# 1-Schematic_GPS_data_logger.net
KiCad netlist of a schematic drawn in EasyEDA
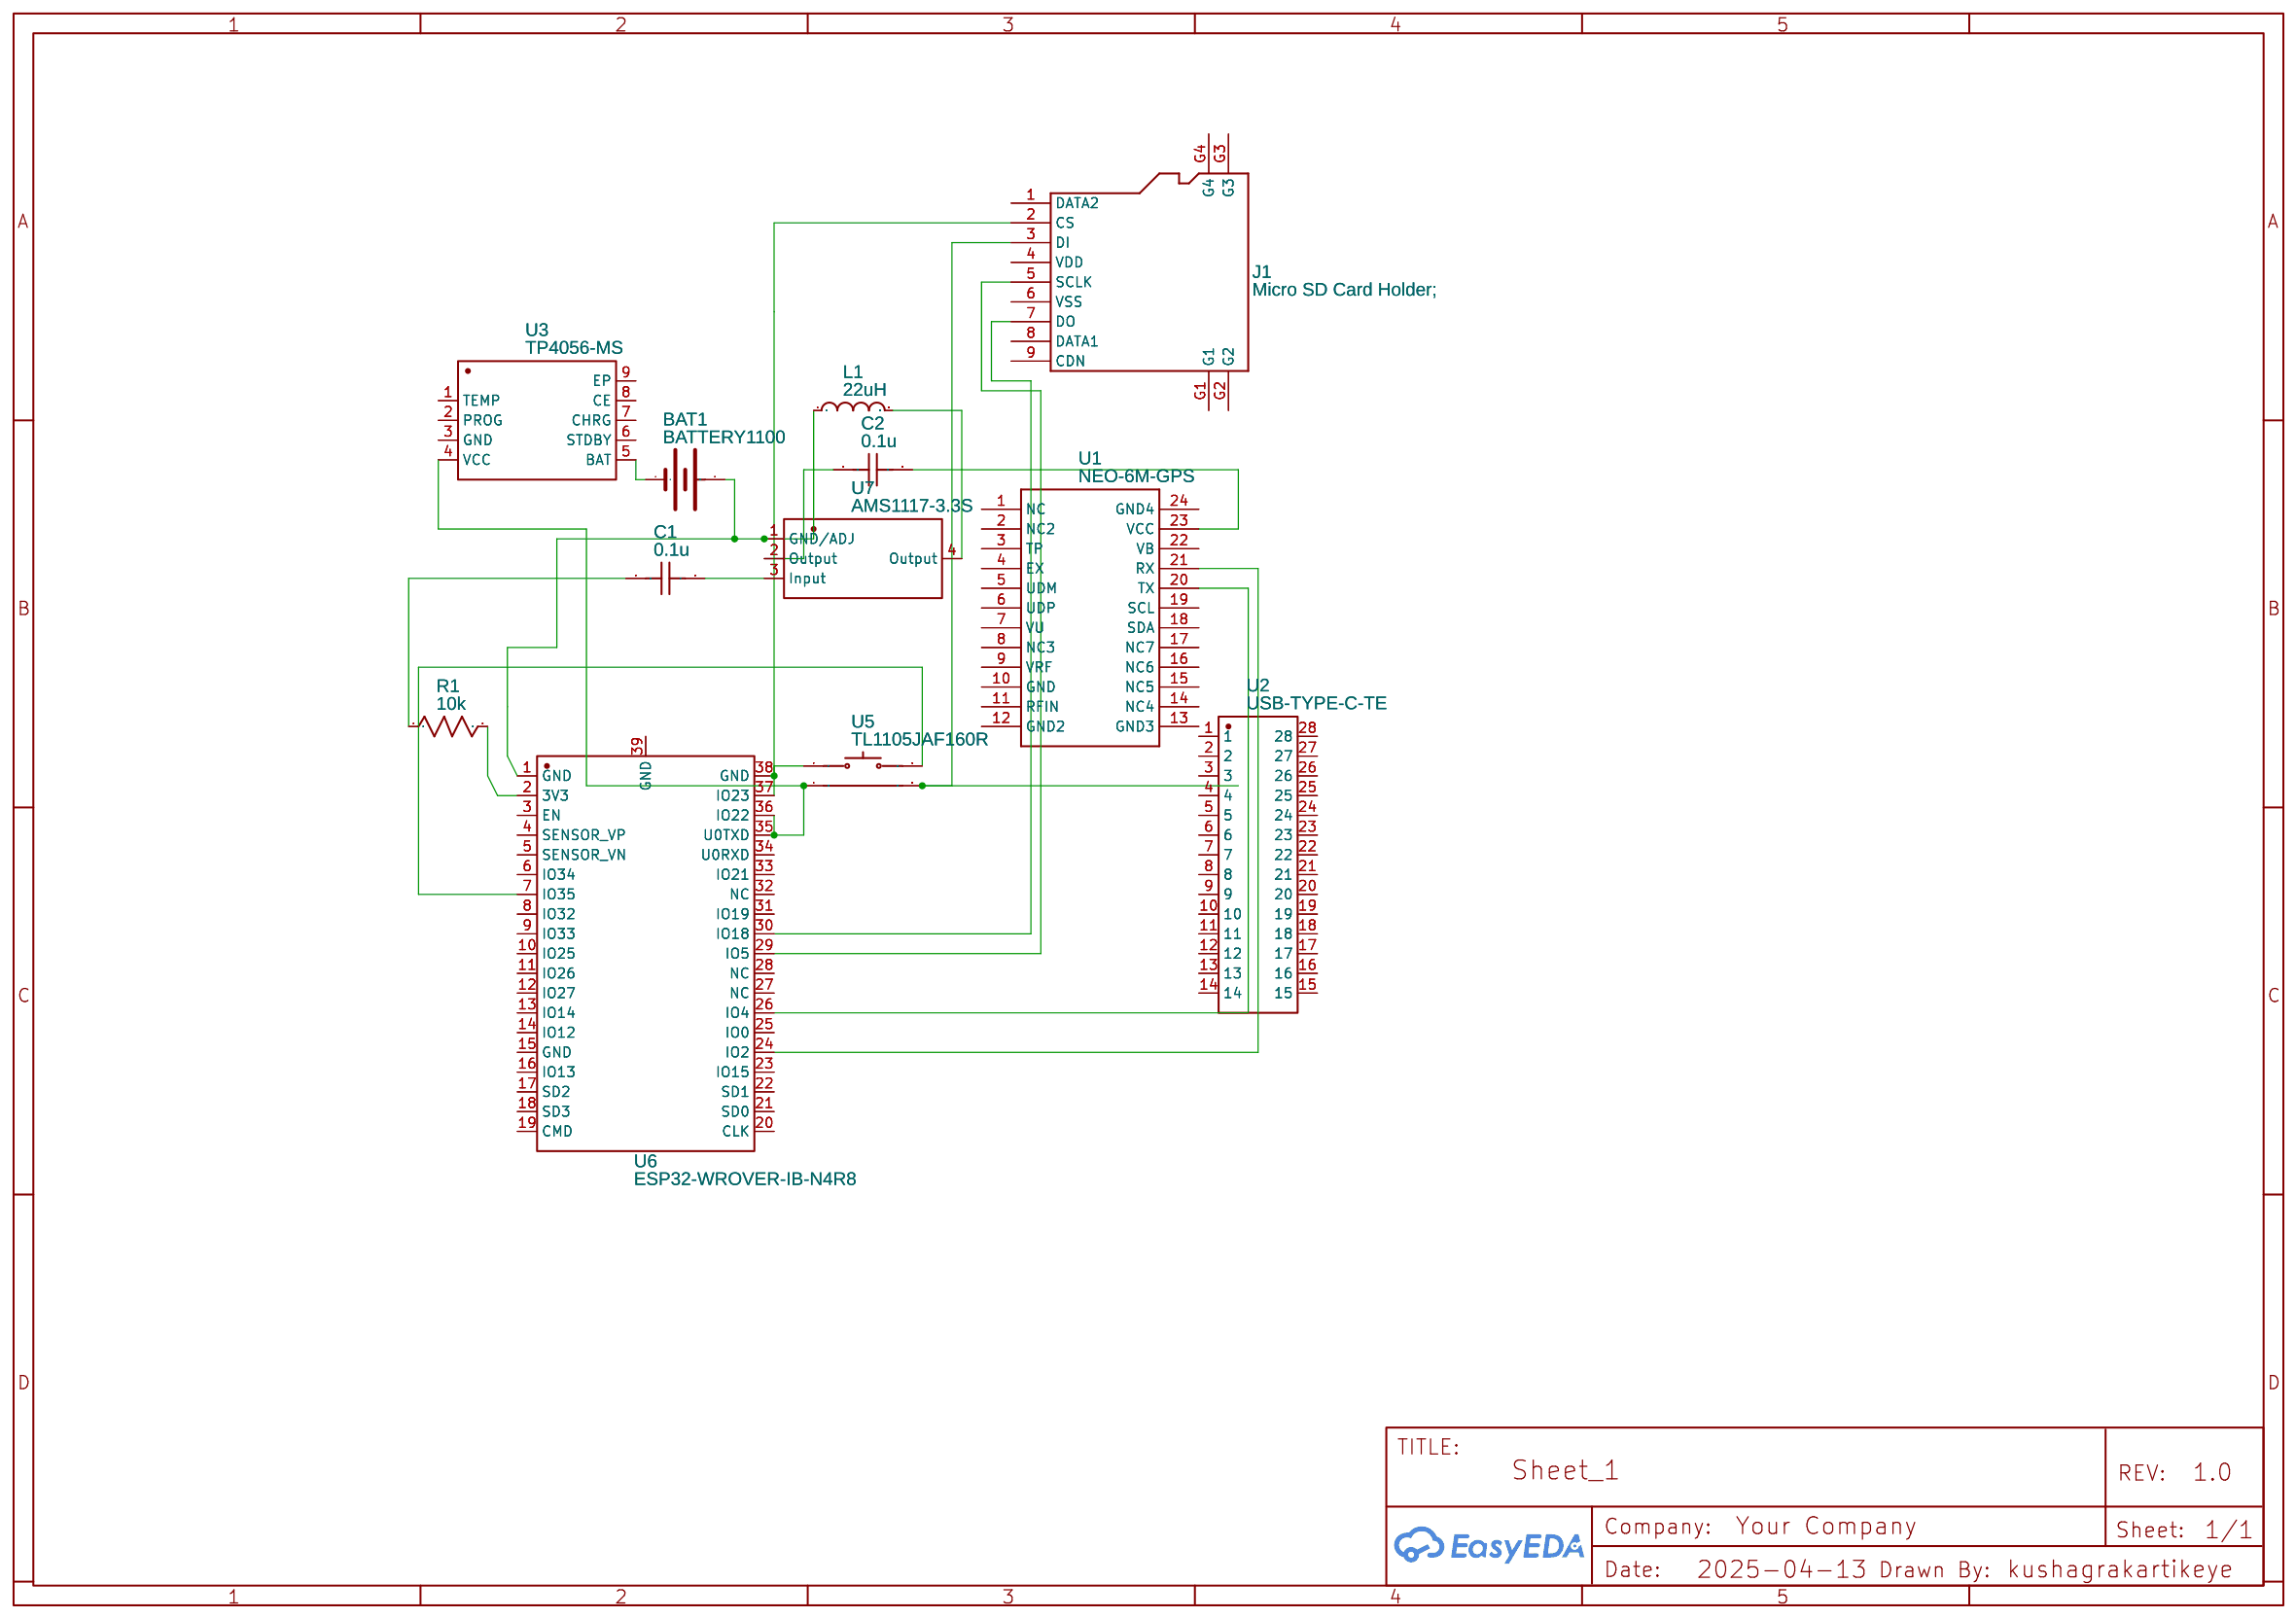
[diagram p0: schematic sheet]

(export (version "E")
  (design (tool "Eeschema 10.0.6"))
  (components
    (comp (ref "BAT1") (value "BATTERY1100") (libsource (lib "") (part "BATTERY1100")))
    (comp (ref "C1") (value "0.1u") (libsource (lib "") (part "C_0603_US")))
    (comp (ref "C2") (value "0.1u") (libsource (lib "") (part "C_0603_US")))
    (comp (ref "J1")
      (value "Micro SD Card Holder;")
      (fields (field (name "Manufacturer Part") "?"))
      (libsource (lib "") (part "Micro SD Card Holder;"))
    )
    (comp (ref "L1")
      (value "22uH")
      (fields
        (field (name "Manufacturer Part") "SSD1306-220MT")
        (field (name "Manufacturer") "LanTu Micro(蓝图微电)")
      )
      (libsource (lib "") (part "SSD1306-220MT"))
    )
    (comp (ref "R1") (value "10k") (libsource (lib "") (part "R_0603_US")))
    (comp (ref "U1") (value "NEO-6M-GPS") (libsource (lib "") (part "NEO-6M-GPS")))
    (comp (ref "U2") (value "USB-TYPE-C-TE") (libsource (lib "") (part "USB-TYPE-C-TE")))
    (comp (ref "U3")
      (value "TP4056-MS")
      (fields (field (name "Manufacturer") "MSKSEMI(美森科)"))
      (libsource (lib "") (part "TP4056-MS"))
    )
    (comp (ref "U5")
      (value "TL1105JAF160R")
      (fields (field (name "Manufacturer") "E-Switch"))
      (libsource (lib "") (part "TL1105JAF160R"))
    )
    (comp (ref "U6")
      (value "ESP32-WROVER-IB-N4R8")
      (fields (field (name "Manufacturer") "ESPRESSIF(乐鑫)"))
      (libsource (lib "") (part "ESP32-WROVER-IB-N4R8"))
    )
    (comp (ref "U7")
      (value "AMS1117-3.3S")
      (fields (field (name "Manufacturer") "KEXIN(科信)"))
      (libsource (lib "") (part "AMS1117-3.3S"))
    )
  )
  (nets
    (net (code "1") (name "Net-(C1-Pad1)") (class "Default")
      (node (ref "C1") (pin "1") (pinfunction "1_1") (pintype "unspecified"))
      (node (ref "R1") (pin "1") (pinfunction "1_1") (pintype "unspecified"))
    )
    (net (code "2") (name "Net-(C2-Pad1)") (class "Default")
      (node (ref "C2") (pin "1") (pinfunction "1_1") (pintype "unspecified"))
      (node (ref "U7") (pin "2") (pinfunction "Output_2") (pintype "unspecified"))
    )
    (net (code "3") (name "Net-(J1-CS)") (class "Default")
      (node (ref "J1") (pin "2") (pinfunction "CS_2") (pintype "unspecified"))
      (node (ref "U5") (pin "1") (pinfunction "1_1") (pintype "input"))
      (node (ref "U6") (pin "37") (pinfunction "IO23_37") (pintype "unspecified"))
      (node (ref "U6") (pin "38") (pinfunction "GND_38") (pintype "unspecified"))
    )
    (net (code "4") (name "Net-(J1-DI)") (class "Default")
      (node (ref "J1") (pin "3") (pinfunction "DI_3") (pintype "unspecified"))
      (node (ref "U5") (pin "3") (pinfunction "3_3") (pintype "input"))
    )
    (net (code "5") (name "Net-(J1-DO)") (class "Default")
      (node (ref "J1") (pin "7") (pinfunction "DO_7") (pintype "unspecified"))
      (node (ref "U6") (pin "30") (pinfunction "IO18_30") (pintype "unspecified"))
    )
    (net (code "6") (name "Net-(J1-SCLK)") (class "Default")
      (node (ref "J1") (pin "5") (pinfunction "SCLK_5") (pintype "unspecified"))
      (node (ref "U6") (pin "29") (pinfunction "IO5_29") (pintype "unspecified"))
    )
    (net (code "7") (name "Net-(L1-Pad2)") (class "Default")
      (node (ref "L1") (pin "2") (pinfunction "2_2") (pintype "unspecified"))
      (node (ref "U7") (pin "4") (pinfunction "Output_4") (pintype "unspecified"))
    )
    (net (code "8") (name "Net-(U1-RX)") (class "Default")
      (node (ref "U1") (pin "21") (pinfunction "RX_21") (pintype "unspecified"))
      (node (ref "U6") (pin "24") (pinfunction "IO2_24") (pintype "unspecified"))
    )
    (net (code "9") (name "Net-(U1-TX)") (class "Default")
      (node (ref "U1") (pin "20") (pinfunction "TX_20") (pintype "unspecified"))
      (node (ref "U6") (pin "26") (pinfunction "IO4_26") (pintype "unspecified"))
    )
    (net (code "10") (name "Net-(U1-VCC)") (class "Default")
      (node (ref "C2") (pin "2") (pinfunction "2_2") (pintype "unspecified"))
      (node (ref "U1") (pin "23") (pinfunction "VCC_23") (pintype "unspecified"))
    )
    (net (code "11") (name "Net-(U3-BAT)") (class "Default")
      (node (ref "BAT1") (pin "-") (pinfunction "-_-") (pintype "passive"))
      (node (ref "U3") (pin "5") (pinfunction "BAT_5") (pintype "unspecified"))
    )
    (net (code "12") (name "Net-(U3-VCC)") (class "Default")
      (node (ref "U3") (pin "4") (pinfunction "VCC_4") (pintype "unspecified"))
      (node (ref "U5") (pin "4") (pinfunction "4_4") (pintype "input"))
      (node (ref "U6") (pin "35") (pinfunction "U0TXD_35") (pintype "unspecified"))
      (node (ref "U6") (pin "36") (pinfunction "IO22_36") (pintype "unspecified"))
    )
    (net (code "13") (name "Net-(U6-3V3)") (class "Default")
      (node (ref "R1") (pin "2") (pinfunction "2_2") (pintype "unspecified"))
      (node (ref "U6") (pin "2") (pinfunction "3V3_2") (pintype "unspecified"))
    )
    (net (code "14") (name "Net-(U6-IO35)") (class "Default")
      (node (ref "U5") (pin "2") (pinfunction "2_2") (pintype "input"))
      (node (ref "U6") (pin "7") (pinfunction "IO35_7") (pintype "unspecified"))
    )
    (net (code "15") (name "Net-(U7-GND{slash}ADJ)") (class "Default")
      (node (ref "BAT1") (pin "+") (pinfunction "+_+") (pintype "passive"))
      (node (ref "L1") (pin "1") (pinfunction "1_1") (pintype "unspecified"))
      (node (ref "U6") (pin "1") (pinfunction "GND_1") (pintype "unspecified"))
      (node (ref "U7") (pin "1") (pinfunction "GND/ADJ_1") (pintype "unspecified"))
    )
    (net (code "16") (name "Net-(U7-Input)") (class "Default")
      (node (ref "C1") (pin "2") (pinfunction "2_2") (pintype "unspecified"))
      (node (ref "U7") (pin "3") (pinfunction "Input_3") (pintype "unspecified"))
    )
    (net (code "17") (name "unconnected-(J1-CDN-Pad9)") (class "Default")
      (node (ref "J1") (pin "9") (pinfunction "CDN_9") (pintype "unspecified"))
    )
    (net (code "18") (name "unconnected-(J1-DATA1-Pad8)") (class "Default")
      (node (ref "J1") (pin "8") (pinfunction "DATA1_8") (pintype "unspecified"))
    )
    (net (code "19") (name "unconnected-(J1-DATA2-Pad1)") (class "Default")
      (node (ref "J1") (pin "1") (pinfunction "DATA2_1") (pintype "unspecified"))
    )
    (net (code "20") (name "unconnected-(J1-PadG1)") (class "Default")
      (node (ref "J1") (pin "G1") (pinfunction "G1_G1") (pintype "unspecified"))
    )
    (net (code "21") (name "unconnected-(J1-PadG2)") (class "Default")
      (node (ref "J1") (pin "G2") (pinfunction "G2_G2") (pintype "unspecified"))
    )
    (net (code "22") (name "unconnected-(J1-PadG3)") (class "Default")
      (node (ref "J1") (pin "G3") (pinfunction "G3_G3") (pintype "unspecified"))
    )
    (net (code "23") (name "unconnected-(J1-PadG4)") (class "Default")
      (node (ref "J1") (pin "G4") (pinfunction "G4_G4") (pintype "unspecified"))
    )
    (net (code "24") (name "unconnected-(J1-VDD-Pad4)") (class "Default")
      (node (ref "J1") (pin "4") (pinfunction "VDD_4") (pintype "unspecified"))
    )
    (net (code "25") (name "unconnected-(J1-VSS-Pad6)") (class "Default")
      (node (ref "J1") (pin "6") (pinfunction "VSS_6") (pintype "unspecified"))
    )
    (net (code "26") (name "unconnected-(U1-EX-Pad4)") (class "Default")
      (node (ref "U1") (pin "4") (pinfunction "EX_4") (pintype "unspecified"))
    )
    (net (code "27") (name "unconnected-(U1-GND-Pad10)") (class "Default")
      (node (ref "U1") (pin "10") (pinfunction "GND_10") (pintype "unspecified"))
    )
    (net (code "28") (name "unconnected-(U1-GND2-Pad12)") (class "Default")
      (node (ref "U1") (pin "12") (pinfunction "GND2_12") (pintype "unspecified"))
    )
    (net (code "29") (name "unconnected-(U1-GND3-Pad13)") (class "Default")
      (node (ref "U1") (pin "13") (pinfunction "GND3_13") (pintype "unspecified"))
    )
    (net (code "30") (name "unconnected-(U1-GND4-Pad24)") (class "Default")
      (node (ref "U1") (pin "24") (pinfunction "GND4_24") (pintype "unspecified"))
    )
    (net (code "31") (name "unconnected-(U1-NC-Pad1)") (class "Default")
      (node (ref "U1") (pin "1") (pinfunction "NC_1") (pintype "unspecified"))
    )
    (net (code "32") (name "unconnected-(U1-NC2-Pad2)") (class "Default")
      (node (ref "U1") (pin "2") (pinfunction "NC2_2") (pintype "unspecified"))
    )
    (net (code "33") (name "unconnected-(U1-NC3-Pad8)") (class "Default")
      (node (ref "U1") (pin "8") (pinfunction "NC3_8") (pintype "unspecified"))
    )
    (net (code "34") (name "unconnected-(U1-NC4-Pad14)") (class "Default")
      (node (ref "U1") (pin "14") (pinfunction "NC4_14") (pintype "unspecified"))
    )
    (net (code "35") (name "unconnected-(U1-NC5-Pad15)") (class "Default")
      (node (ref "U1") (pin "15") (pinfunction "NC5_15") (pintype "unspecified"))
    )
    (net (code "36") (name "unconnected-(U1-NC6-Pad16)") (class "Default")
      (node (ref "U1") (pin "16") (pinfunction "NC6_16") (pintype "unspecified"))
    )
    (net (code "37") (name "unconnected-(U1-NC7-Pad17)") (class "Default")
      (node (ref "U1") (pin "17") (pinfunction "NC7_17") (pintype "unspecified"))
    )
    (net (code "38") (name "unconnected-(U1-RFIN-Pad11)") (class "Default")
      (node (ref "U1") (pin "11") (pinfunction "RFIN_11") (pintype "unspecified"))
    )
    (net (code "39") (name "unconnected-(U1-SCL-Pad19)") (class "Default")
      (node (ref "U1") (pin "19") (pinfunction "SCL_19") (pintype "unspecified"))
    )
    (net (code "40") (name "unconnected-(U1-SDA-Pad18)") (class "Default")
      (node (ref "U1") (pin "18") (pinfunction "SDA_18") (pintype "unspecified"))
    )
    (net (code "41") (name "unconnected-(U1-TP-Pad3)") (class "Default")
      (node (ref "U1") (pin "3") (pinfunction "TP_3") (pintype "unspecified"))
    )
    (net (code "42") (name "unconnected-(U1-UDM-Pad5)") (class "Default")
      (node (ref "U1") (pin "5") (pinfunction "UDM_5") (pintype "unspecified"))
    )
    (net (code "43") (name "unconnected-(U1-UDP-Pad6)") (class "Default")
      (node (ref "U1") (pin "6") (pinfunction "UDP_6") (pintype "unspecified"))
    )
    (net (code "44") (name "unconnected-(U1-VB-Pad22)") (class "Default")
      (node (ref "U1") (pin "22") (pinfunction "VB_22") (pintype "unspecified"))
    )
    (net (code "45") (name "unconnected-(U1-VRF-Pad9)") (class "Default")
      (node (ref "U1") (pin "9") (pinfunction "VRF_9") (pintype "unspecified"))
    )
    (net (code "46") (name "unconnected-(U1-VU-Pad7)") (class "Default")
      (node (ref "U1") (pin "7") (pinfunction "VU_7") (pintype "unspecified"))
    )
    (net (code "47") (name "unconnected-(U2-Pad1)") (class "Default")
      (node (ref "U2") (pin "1") (pinfunction "1_1") (pintype "unspecified"))
    )
    (net (code "48") (name "unconnected-(U2-Pad2)") (class "Default")
      (node (ref "U2") (pin "2") (pinfunction "2_2") (pintype "unspecified"))
    )
    (net (code "49") (name "unconnected-(U2-Pad3)") (class "Default")
      (node (ref "U2") (pin "3") (pinfunction "3_3") (pintype "unspecified"))
    )
    (net (code "50") (name "unconnected-(U2-Pad4)") (class "Default")
      (node (ref "U2") (pin "4") (pinfunction "4_4") (pintype "unspecified"))
    )
    (net (code "51") (name "unconnected-(U2-Pad5)") (class "Default")
      (node (ref "U2") (pin "5") (pinfunction "5_5") (pintype "unspecified"))
    )
    (net (code "52") (name "unconnected-(U2-Pad6)") (class "Default")
      (node (ref "U2") (pin "6") (pinfunction "6_6") (pintype "unspecified"))
    )
    (net (code "53") (name "unconnected-(U2-Pad7)") (class "Default")
      (node (ref "U2") (pin "7") (pinfunction "7_7") (pintype "unspecified"))
    )
    (net (code "54") (name "unconnected-(U2-Pad8)") (class "Default")
      (node (ref "U2") (pin "8") (pinfunction "8_8") (pintype "unspecified"))
    )
    (net (code "55") (name "unconnected-(U2-Pad9)") (class "Default")
      (node (ref "U2") (pin "9") (pinfunction "9_9") (pintype "unspecified"))
    )
    (net (code "56") (name "unconnected-(U2-Pad10)") (class "Default")
      (node (ref "U2") (pin "10") (pinfunction "10_10") (pintype "unspecified"))
    )
    (net (code "57") (name "unconnected-(U2-Pad11)") (class "Default")
      (node (ref "U2") (pin "11") (pinfunction "11_11") (pintype "unspecified"))
    )
    (net (code "58") (name "unconnected-(U2-Pad12)") (class "Default")
      (node (ref "U2") (pin "12") (pinfunction "12_12") (pintype "unspecified"))
    )
    (net (code "59") (name "unconnected-(U2-Pad13)") (class "Default")
      (node (ref "U2") (pin "13") (pinfunction "13_13") (pintype "unspecified"))
    )
    (net (code "60") (name "unconnected-(U2-Pad14)") (class "Default")
      (node (ref "U2") (pin "14") (pinfunction "14_14") (pintype "unspecified"))
    )
    (net (code "61") (name "unconnected-(U2-Pad15)") (class "Default")
      (node (ref "U2") (pin "15") (pinfunction "15_15") (pintype "unspecified"))
    )
    (net (code "62") (name "unconnected-(U2-Pad16)") (class "Default")
      (node (ref "U2") (pin "16") (pinfunction "16_16") (pintype "unspecified"))
    )
    (net (code "63") (name "unconnected-(U2-Pad17)") (class "Default")
      (node (ref "U2") (pin "17") (pinfunction "17_17") (pintype "unspecified"))
    )
    (net (code "64") (name "unconnected-(U2-Pad18)") (class "Default")
      (node (ref "U2") (pin "18") (pinfunction "18_18") (pintype "unspecified"))
    )
    (net (code "65") (name "unconnected-(U2-Pad19)") (class "Default")
      (node (ref "U2") (pin "19") (pinfunction "19_19") (pintype "unspecified"))
    )
    (net (code "66") (name "unconnected-(U2-Pad20)") (class "Default")
      (node (ref "U2") (pin "20") (pinfunction "20_20") (pintype "unspecified"))
    )
    (net (code "67") (name "unconnected-(U2-Pad21)") (class "Default")
      (node (ref "U2") (pin "21") (pinfunction "21_21") (pintype "unspecified"))
    )
    (net (code "68") (name "unconnected-(U2-Pad22)") (class "Default")
      (node (ref "U2") (pin "22") (pinfunction "22_22") (pintype "unspecified"))
    )
    (net (code "69") (name "unconnected-(U2-Pad23)") (class "Default")
      (node (ref "U2") (pin "23") (pinfunction "23_23") (pintype "unspecified"))
    )
    (net (code "70") (name "unconnected-(U2-Pad24)") (class "Default")
      (node (ref "U2") (pin "24") (pinfunction "24_24") (pintype "unspecified"))
    )
    (net (code "71") (name "unconnected-(U2-Pad25)") (class "Default")
      (node (ref "U2") (pin "25") (pinfunction "25_25") (pintype "unspecified"))
    )
    (net (code "72") (name "unconnected-(U2-Pad26)") (class "Default")
      (node (ref "U2") (pin "26") (pinfunction "26_26") (pintype "unspecified"))
    )
    (net (code "73") (name "unconnected-(U2-Pad27)") (class "Default")
      (node (ref "U2") (pin "27") (pinfunction "27_27") (pintype "unspecified"))
    )
    (net (code "74") (name "unconnected-(U2-Pad28)") (class "Default")
      (node (ref "U2") (pin "28") (pinfunction "28_28") (pintype "unspecified"))
    )
    (net (code "75") (name "unconnected-(U3-CE-Pad8)") (class "Default")
      (node (ref "U3") (pin "8") (pinfunction "CE_8") (pintype "unspecified"))
    )
    (net (code "76") (name "unconnected-(U3-CHRG-Pad7)") (class "Default")
      (node (ref "U3") (pin "7") (pinfunction "CHRG_7") (pintype "unspecified"))
    )
    (net (code "77") (name "unconnected-(U3-EP-Pad9)") (class "Default")
      (node (ref "U3") (pin "9") (pinfunction "EP_9") (pintype "unspecified"))
    )
    (net (code "78") (name "unconnected-(U3-GND-Pad3)") (class "Default")
      (node (ref "U3") (pin "3") (pinfunction "GND_3") (pintype "unspecified"))
    )
    (net (code "79") (name "unconnected-(U3-PROG-Pad2)") (class "Default")
      (node (ref "U3") (pin "2") (pinfunction "PROG_2") (pintype "unspecified"))
    )
    (net (code "80") (name "unconnected-(U3-STDBY-Pad6)") (class "Default")
      (node (ref "U3") (pin "6") (pinfunction "STDBY_6") (pintype "unspecified"))
    )
    (net (code "81") (name "unconnected-(U3-TEMP-Pad1)") (class "Default")
      (node (ref "U3") (pin "1") (pinfunction "TEMP_1") (pintype "unspecified"))
    )
    (net (code "82") (name "unconnected-(U6-CLK-Pad20)") (class "Default")
      (node (ref "U6") (pin "20") (pinfunction "CLK_20") (pintype "unspecified"))
    )
    (net (code "83") (name "unconnected-(U6-CMD-Pad19)") (class "Default")
      (node (ref "U6") (pin "19") (pinfunction "CMD_19") (pintype "unspecified"))
    )
    (net (code "84") (name "unconnected-(U6-EN-Pad3)") (class "Default")
      (node (ref "U6") (pin "3") (pinfunction "EN_3") (pintype "unspecified"))
    )
    (net (code "85") (name "unconnected-(U6-GND-Pad15)") (class "Default")
      (node (ref "U6") (pin "15") (pinfunction "GND_15") (pintype "unspecified"))
    )
    (net (code "86") (name "unconnected-(U6-GND-Pad39)") (class "Default")
      (node (ref "U6") (pin "39") (pinfunction "GND_39") (pintype "unspecified"))
    )
    (net (code "87") (name "unconnected-(U6-IO0-Pad25)") (class "Default")
      (node (ref "U6") (pin "25") (pinfunction "IO0_25") (pintype "unspecified"))
    )
    (net (code "88") (name "unconnected-(U6-IO12-Pad14)") (class "Default")
      (node (ref "U6") (pin "14") (pinfunction "IO12_14") (pintype "unspecified"))
    )
    (net (code "89") (name "unconnected-(U6-IO13-Pad16)") (class "Default")
      (node (ref "U6") (pin "16") (pinfunction "IO13_16") (pintype "unspecified"))
    )
    (net (code "90") (name "unconnected-(U6-IO14-Pad13)") (class "Default")
      (node (ref "U6") (pin "13") (pinfunction "IO14_13") (pintype "unspecified"))
    )
    (net (code "91") (name "unconnected-(U6-IO15-Pad23)") (class "Default")
      (node (ref "U6") (pin "23") (pinfunction "IO15_23") (pintype "unspecified"))
    )
    (net (code "92") (name "unconnected-(U6-IO19-Pad31)") (class "Default")
      (node (ref "U6") (pin "31") (pinfunction "IO19_31") (pintype "unspecified"))
    )
    (net (code "93") (name "unconnected-(U6-IO21-Pad33)") (class "Default")
      (node (ref "U6") (pin "33") (pinfunction "IO21_33") (pintype "unspecified"))
    )
    (net (code "94") (name "unconnected-(U6-IO25-Pad10)") (class "Default")
      (node (ref "U6") (pin "10") (pinfunction "IO25_10") (pintype "unspecified"))
    )
    (net (code "95") (name "unconnected-(U6-IO26-Pad11)") (class "Default")
      (node (ref "U6") (pin "11") (pinfunction "IO26_11") (pintype "unspecified"))
    )
    (net (code "96") (name "unconnected-(U6-IO27-Pad12)") (class "Default")
      (node (ref "U6") (pin "12") (pinfunction "IO27_12") (pintype "unspecified"))
    )
    (net (code "97") (name "unconnected-(U6-IO32-Pad8)") (class "Default")
      (node (ref "U6") (pin "8") (pinfunction "IO32_8") (pintype "unspecified"))
    )
    (net (code "98") (name "unconnected-(U6-IO33-Pad9)") (class "Default")
      (node (ref "U6") (pin "9") (pinfunction "IO33_9") (pintype "unspecified"))
    )
    (net (code "99") (name "unconnected-(U6-IO34-Pad6)") (class "Default")
      (node (ref "U6") (pin "6") (pinfunction "IO34_6") (pintype "unspecified"))
    )
    (net (code "100") (name "unconnected-(U6-NC-Pad27)") (class "Default")
      (node (ref "U6") (pin "27") (pinfunction "NC_27") (pintype "unspecified"))
    )
    (net (code "101") (name "unconnected-(U6-NC-Pad28)") (class "Default")
      (node (ref "U6") (pin "28") (pinfunction "NC_28") (pintype "unspecified"))
    )
    (net (code "102") (name "unconnected-(U6-NC-Pad32)") (class "Default")
      (node (ref "U6") (pin "32") (pinfunction "NC_32") (pintype "unspecified"))
    )
    (net (code "103") (name "unconnected-(U6-SD0-Pad21)") (class "Default")
      (node (ref "U6") (pin "21") (pinfunction "SD0_21") (pintype "unspecified"))
    )
    (net (code "104") (name "unconnected-(U6-SD1-Pad22)") (class "Default")
      (node (ref "U6") (pin "22") (pinfunction "SD1_22") (pintype "unspecified"))
    )
    (net (code "105") (name "unconnected-(U6-SD2-Pad17)") (class "Default")
      (node (ref "U6") (pin "17") (pinfunction "SD2_17") (pintype "unspecified"))
    )
    (net (code "106") (name "unconnected-(U6-SD3-Pad18)") (class "Default")
      (node (ref "U6") (pin "18") (pinfunction "SD3_18") (pintype "unspecified"))
    )
    (net (code "107") (name "unconnected-(U6-SENSOR_VN-Pad5)") (class "Default")
      (node (ref "U6") (pin "5") (pinfunction "SENSOR_VN_5") (pintype "unspecified"))
    )
    (net (code "108") (name "unconnected-(U6-SENSOR_VP-Pad4)") (class "Default")
      (node (ref "U6") (pin "4") (pinfunction "SENSOR_VP_4") (pintype "unspecified"))
    )
    (net (code "109") (name "unconnected-(U6-U0RXD-Pad34)") (class "Default")
      (node (ref "U6") (pin "34") (pinfunction "U0RXD_34") (pintype "unspecified"))
    )
  )
)
